# Adafruit_Feather_RP2040_Scorpio.net
KiCad netlist of a schematic drawn in EAGLE
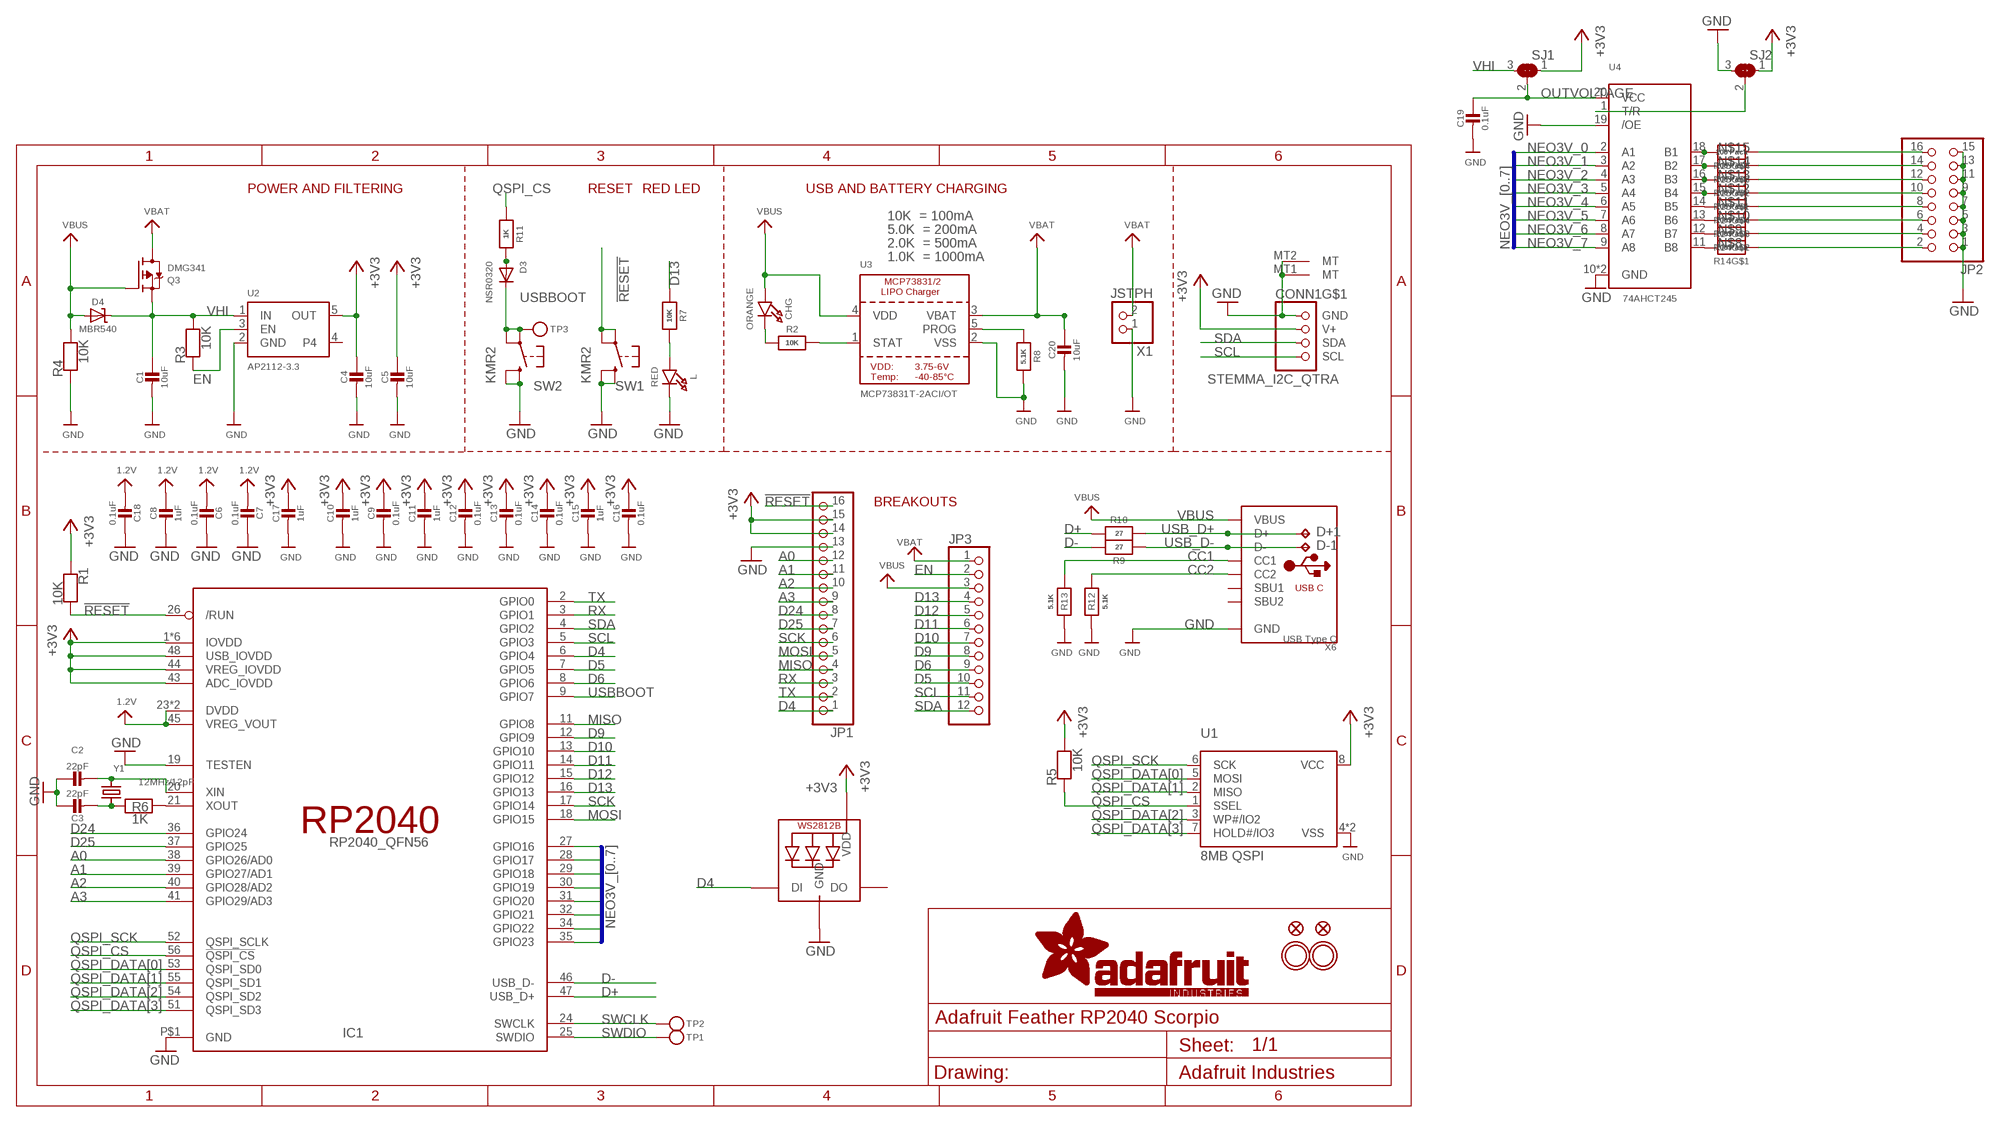
[diagram p0: schematic, sheet 1]

(export (version "E")
  (design (tool "Eeschema 10.0.6"))
  (components
    (comp (ref "C1")
      (value "10uF")
      (footprint "eagle-import:0805-NO")
      (libsource (lib "eagle-import") (part "CAP_CERAMIC0805-NOOUTLINE"))
    )
    (comp (ref "C2")
      (value "22pF")
      (footprint "eagle-import:_0402NO")
      (libsource (lib "eagle-import") (part "CAP_CERAMIC_0402NO"))
    )
    (comp (ref "C3")
      (value "22pF")
      (footprint "eagle-import:_0402NO")
      (libsource (lib "eagle-import") (part "CAP_CERAMIC_0402NO"))
    )
    (comp (ref "C4")
      (value "10uF")
      (footprint "eagle-import:0805-NO")
      (fields (field (name "REV") "A"))
      (libsource (lib "eagle-import") (part "CAP_CERAMIC0805-NOOUTLINE"))
    )
    (comp (ref "C5")
      (value "10uF")
      (footprint "eagle-import:0805-NO")
      (libsource (lib "eagle-import") (part "CAP_CERAMIC0805-NOOUTLINE"))
    )
    (comp (ref "C6")
      (value "0.1uF")
      (footprint "eagle-import:_0402NO")
      (libsource (lib "eagle-import") (part "CAP_CERAMIC_0402NO"))
    )
    (comp (ref "C7")
      (value "0.1uF")
      (footprint "eagle-import:_0402NO")
      (libsource (lib "eagle-import") (part "CAP_CERAMIC_0402NO"))
    )
    (comp (ref "C8")
      (value "1uF")
      (footprint "eagle-import:0603-NO")
      (libsource (lib "eagle-import") (part "CAP_CERAMIC0603_NO"))
    )
    (comp (ref "C9")
      (value "0.1uF")
      (footprint "eagle-import:_0402NO")
      (libsource (lib "eagle-import") (part "CAP_CERAMIC_0402NO"))
    )
    (comp (ref "C10")
      (value "1uF")
      (footprint "eagle-import:0603-NO")
      (libsource (lib "eagle-import") (part "CAP_CERAMIC0603_NO"))
    )
    (comp (ref "C11")
      (value "1uF")
      (footprint "eagle-import:0603-NO")
      (libsource (lib "eagle-import") (part "CAP_CERAMIC0603_NO"))
    )
    (comp (ref "C12")
      (value "0.1uF")
      (footprint "eagle-import:_0402NO")
      (libsource (lib "eagle-import") (part "CAP_CERAMIC_0402NO"))
    )
    (comp (ref "C13")
      (value "0.1uF")
      (footprint "eagle-import:_0402NO")
      (libsource (lib "eagle-import") (part "CAP_CERAMIC_0402NO"))
    )
    (comp (ref "C14")
      (value "0.1uF")
      (footprint "eagle-import:_0402NO")
      (libsource (lib "eagle-import") (part "CAP_CERAMIC_0402NO"))
    )
    (comp (ref "C15")
      (value "1uF")
      (footprint "eagle-import:0603-NO")
      (libsource (lib "eagle-import") (part "CAP_CERAMIC0603_NO"))
    )
    (comp (ref "C16")
      (value "0.1uF")
      (footprint "eagle-import:_0402NO")
      (libsource (lib "eagle-import") (part "CAP_CERAMIC_0402NO"))
    )
    (comp (ref "C17")
      (value "1uF")
      (footprint "eagle-import:0603-NO")
      (libsource (lib "eagle-import") (part "CAP_CERAMIC0603_NO"))
    )
    (comp (ref "C18")
      (value "0.1uF")
      (footprint "eagle-import:_0402NO")
      (libsource (lib "eagle-import") (part "CAP_CERAMIC_0402NO"))
    )
    (comp (ref "C19")
      (value "0.1uF")
      (footprint "eagle-import:_0402NO")
      (libsource (lib "eagle-import") (part "CAP_CERAMIC_0402NO"))
    )
    (comp (ref "C20")
      (value "10uF")
      (footprint "eagle-import:0805-NO")
      (libsource (lib "eagle-import") (part "CAP_CERAMIC0805-NOOUTLINE"))
    )
    (comp (ref "CHG")
      (value "ORANGE")
      (footprint "eagle-import:CHIPLED_0603_NOOUTLINE")
      (libsource (lib "eagle-import") (part "LED0603_NOOUTLINE"))
    )
    (comp (ref "CONN1")
      (value "STEMMA_I2C_QTRA")
      (footprint "eagle-import:JST_SH4_RA")
      (libsource (lib "eagle-import") (part "STEMMA_I2C_QTRA"))
    )
    (comp (ref "D+1")
      (value "TPB1,27")
      (footprint "eagle-import:B1,27")
      (libsource (lib "eagle-import") (part "TPB1,27"))
    )
    (comp (ref "D-1")
      (value "TPB1,27")
      (footprint "eagle-import:B1,27")
      (libsource (lib "eagle-import") (part "TPB1,27"))
    )
    (comp (ref "D3")
      (value "NSR0320")
      (footprint "eagle-import:SOD-323F")
      (libsource (lib "eagle-import") (part "DIODESOD-323F"))
    )
    (comp (ref "D4")
      (value "MBR540")
      (footprint "eagle-import:SOD-123")
      (libsource (lib "eagle-import") (part "DIODE-SCHOTTKYSOD-123"))
    )
    (comp (ref "IC1")
      (value "RP2040_QFN56")
      (footprint "eagle-import:QFN56_7MM_REDUCEDEPAD")
      (libsource (lib "eagle-import") (part "RP2040_QFN56"))
    )
    (comp (ref "JP1")
      (value "HEADER-1X16ROUND")
      (footprint "eagle-import:1X16_ROUND")
      (libsource (lib "eagle-import") (part "HEADER-1X16ROUND"))
    )
    (comp (ref "JP2")
      (value "HEADER-2X8")
      (footprint "eagle-import:2X08")
      (libsource (lib "eagle-import") (part "HEADER-2X8"))
    )
    (comp (ref "JP3")
      (value "HEADER-1X12")
      (footprint "eagle-import:1X12_ROUND")
      (libsource (lib "eagle-import") (part "HEADER-1X12"))
    )
    (comp (ref "L")
      (value "RED")
      (footprint "eagle-import:CHIPLED_0603_NOOUTLINE")
      (libsource (lib "eagle-import") (part "LED0603_NOOUTLINE"))
    )
    (comp (ref "LED1")
      (value "WS2812B_SK6805_1515")
      (footprint "eagle-import:SK6805_1515")
      (libsource (lib "eagle-import") (part "WS2812B_SK6805_1515"))
    )
    (comp (ref "Q3")
      (value "DMG341")
      (footprint "eagle-import:SOT23-R")
      (libsource (lib "eagle-import") (part "MOSFET-P"))
    )
    (comp (ref "R1")
      (value "10K")
      (footprint "eagle-import:0603-NO")
      (libsource (lib "eagle-import") (part "RESISTOR_0603_NOOUT"))
    )
    (comp (ref "R2")
      (value "10K")
      (footprint "eagle-import:0603-NO")
      (libsource (lib "eagle-import") (part "RESISTOR_0603_NOOUT"))
    )
    (comp (ref "R3")
      (value "10K")
      (footprint "eagle-import:0603-NO")
      (libsource (lib "eagle-import") (part "RESISTOR_0603_NOOUT"))
    )
    (comp (ref "R4")
      (value "10K")
      (footprint "eagle-import:0603-NO")
      (libsource (lib "eagle-import") (part "RESISTOR_0603_NOOUT"))
    )
    (comp (ref "R5")
      (value "10K")
      (footprint "eagle-import:0603-NO")
      (libsource (lib "eagle-import") (part "RESISTOR_0603_NOOUT"))
    )
    (comp (ref "R6")
      (value "1K")
      (footprint "eagle-import:0603-NO")
      (libsource (lib "eagle-import") (part "RESISTOR_0603_NOOUT"))
    )
    (comp (ref "R7")
      (value "10K")
      (footprint "eagle-import:0603-NO")
      (libsource (lib "eagle-import") (part "RESISTOR_0603_NOOUT"))
    )
    (comp (ref "R8")
      (value "5.1K")
      (footprint "eagle-import:0603-NO")
      (libsource (lib "eagle-import") (part "RESISTOR_0603_NOOUT"))
    )
    (comp (ref "R9")
      (value "27")
      (footprint "eagle-import:0603-NO")
      (libsource (lib "eagle-import") (part "RESISTOR_0603_NOOUT"))
    )
    (comp (ref "R10")
      (value "27")
      (footprint "eagle-import:0603-NO")
      (libsource (lib "eagle-import") (part "RESISTOR_0603_NOOUT"))
    )
    (comp (ref "R11")
      (value "1K")
      (footprint "eagle-import:0603-NO")
      (libsource (lib "eagle-import") (part "RESISTOR_0603_NOOUT"))
    )
    (comp (ref "R12")
      (value "5.1K")
      (footprint "eagle-import:0603-NO")
      (libsource (lib "eagle-import") (part "RESISTOR_0603_NOOUT"))
    )
    (comp (ref "R13")
      (value "5.1K")
      (footprint "eagle-import:0603-NO")
      (libsource (lib "eagle-import") (part "RESISTOR_0603_NOOUT"))
    )
    (comp (ref "R14")
      (value "100 Pack")
      (footprint "eagle-import:RESPACK_4X0402")
      (libsource (lib "eagle-import") (part "RESISTOR_4PACK_0804"))
    )
    (comp (ref "R15")
      (value "100 Pack")
      (footprint "eagle-import:RESPACK_4X0402")
      (libsource (lib "eagle-import") (part "RESISTOR_4PACK_0804"))
    )
    (comp (ref "SJ1")
      (value "SOLDERJUMPER_2WAY")
      (footprint "eagle-import:SOLDERJUMPER_2WAY_OPEN_NOPASTE")
      (libsource (lib "eagle-import") (part "SOLDERJUMPER_2WAY"))
    )
    (comp (ref "SJ2")
      (value "SOLDERJUMPER_2WAY")
      (footprint "eagle-import:SOLDERJUMPER_2WAY_OPEN_NOPASTE")
      (libsource (lib "eagle-import") (part "SOLDERJUMPER_2WAY"))
    )
    (comp (ref "SW1")
      (value "KMR2")
      (footprint "eagle-import:BTN_KMR2_4.6X2.8")
      (libsource (lib "eagle-import") (part "SWITCH_TACT_SMT4.6X2.8"))
    )
    (comp (ref "SW2")
      (value "KMR2")
      (footprint "eagle-import:BTN_KMR2_4.6X2.8")
      (libsource (lib "eagle-import") (part "SWITCH_TACT_SMT4.6X2.8"))
    )
    (comp (ref "TP1")
      (value "TESTPOINTROUND1.5MMNO")
      (footprint "eagle-import:TESTPOINT_ROUND_1.5MM_NO")
      (libsource (lib "eagle-import") (part "TESTPOINTROUND1.5MMNO"))
    )
    (comp (ref "TP2")
      (value "TESTPOINTROUND1.5MMNO")
      (footprint "eagle-import:TESTPOINT_ROUND_1.5MM_NO")
      (libsource (lib "eagle-import") (part "TESTPOINTROUND1.5MMNO"))
    )
    (comp (ref "TP3")
      (value "TESTPOINTROUND1.5MMNO")
      (footprint "eagle-import:TESTPOINT_ROUND_1.5MM_NO")
      (libsource (lib "eagle-import") (part "TESTPOINTROUND1.5MMNO"))
    )
    (comp (ref "U$31")
      (value "MOUNTINGHOLE2.5")
      (footprint "eagle-import:MOUNTINGHOLE_2.5_PLATED")
      (libsource (lib "eagle-import") (part "MOUNTINGHOLE2.5"))
    )
    (comp (ref "U$32")
      (value "MOUNTINGHOLE2.5")
      (footprint "eagle-import:MOUNTINGHOLE_2.5_PLATED")
      (libsource (lib "eagle-import") (part "MOUNTINGHOLE2.5"))
    )
    (comp (ref "U$34")
      (value "FIDUCIAL_1MM")
      (footprint "eagle-import:FIDUCIAL_1MM")
      (libsource (lib "eagle-import") (part "FIDUCIAL_1MM"))
    )
    (comp (ref "U$35")
      (value "FIDUCIAL_1MM")
      (footprint "eagle-import:FIDUCIAL_1MM")
      (libsource (lib "eagle-import") (part "FIDUCIAL_1MM"))
    )
    (comp (ref "U1")
      (value "8MB QSPI")
      (footprint "eagle-import:USON8_4X4")
      (libsource (lib "eagle-import") (part "SPIFLASH_8PIN_4X4"))
    )
    (comp (ref "U2")
      (value "AP2112-3.3")
      (footprint "eagle-import:SOT23-5")
      (fields (field (name "JLC_ROTATION") "0"))
      (libsource (lib "eagle-import") (part "VREG_SOT23-5"))
    )
    (comp (ref "U3")
      (value "MCP73831T-2ACI/OT")
      (footprint "eagle-import:SOT23-5")
      (libsource (lib "eagle-import") (part "MCP73831/2"))
    )
    (comp (ref "U4")
      (value "74AHCT245")
      (footprint "eagle-import:20-DHVQFN")
      (libsource (lib "eagle-import") (part "74LCX245_QFN20"))
    )
    (comp (ref "X1")
      (value "JSTPH")
      (footprint "eagle-import:JSTPH2_BATT")
      (libsource (lib "eagle-import") (part "CON_JST_PH_2PIN_BATT"))
    )
    (comp (ref "X6")
      (value "USB Type C")
      (footprint "eagle-import:USB_C_CUSB31-CFM2AX-01-X")
      (libsource (lib "eagle-import") (part "USB_C"))
    )
    (comp (ref "Y1")
      (value "12MHz/12pF")
      (footprint "eagle-import:CRYSTAL_2.5X2")
      (libsource (lib "eagle-import") (part "CRYSTAL2.5X2.0"))
    )
  )
  (nets
    (net (code "1") (name "+3V3") (class "Default")
      (node (ref "C10") (pin "1") (pinfunction "1_1") (pintype "passive"))
      (node (ref "C11") (pin "1") (pinfunction "1_1") (pintype "passive"))
      (node (ref "C12") (pin "1") (pinfunction "1_1") (pintype "passive"))
      (node (ref "C13") (pin "1") (pinfunction "1_1") (pintype "passive"))
      (node (ref "C14") (pin "1") (pinfunction "1_1") (pintype "passive"))
      (node (ref "C15") (pin "1") (pinfunction "1_1") (pintype "passive"))
      (node (ref "C16") (pin "1") (pinfunction "1_1") (pintype "passive"))
      (node (ref "C17") (pin "1") (pinfunction "1_1") (pintype "passive"))
      (node (ref "C4") (pin "1") (pinfunction "1_1") (pintype "passive"))
      (node (ref "C5") (pin "1") (pinfunction "1_1") (pintype "passive"))
      (node (ref "C9") (pin "1") (pinfunction "1_1") (pintype "passive"))
      (node (ref "CONN1") (pin "2") (pinfunction "V+_2") (pintype "passive"))
      (node (ref "IC1") (pin "1") (pinfunction "IOVDD_1") (pintype "power_in"))
      (node (ref "IC1") (pin "10") (pinfunction "IOVDD_10") (pintype "power_in"))
      (node (ref "IC1") (pin "22") (pinfunction "IOVDD_22") (pintype "power_in"))
      (node (ref "IC1") (pin "33") (pinfunction "IOVDD_33") (pintype "power_in"))
      (node (ref "IC1") (pin "42") (pinfunction "IOVDD_42") (pintype "power_in"))
      (node (ref "IC1") (pin "43") (pinfunction "ADC_IOVDD_43") (pintype "power_in"))
      (node (ref "IC1") (pin "44") (pinfunction "VREG_IOVDD_44") (pintype "power_in"))
      (node (ref "IC1") (pin "48") (pinfunction "USB_IOVDD_48") (pintype "power_in"))
      (node (ref "IC1") (pin "49") (pinfunction "IOVDD_49") (pintype "power_in"))
      (node (ref "JP1") (pin "14") (pinfunction "14_14") (pintype "passive"))
      (node (ref "JP1") (pin "15") (pinfunction "15_15") (pintype "passive"))
      (node (ref "LED1") (pin "2") (pinfunction "VDD_2") (pintype "power_in"))
      (node (ref "R1") (pin "1") (pinfunction "1_1") (pintype "passive"))
      (node (ref "R5") (pin "2") (pinfunction "2_2") (pintype "passive"))
      (node (ref "SJ1") (pin "1") (pinfunction "1_1") (pintype "passive"))
      (node (ref "SJ2") (pin "1") (pinfunction "1_1") (pintype "passive"))
      (node (ref "U1") (pin "8") (pinfunction "VCC_8") (pintype "bidirectional"))
      (node (ref "U2") (pin "5") (pinfunction "OUT_5") (pintype "power_in"))
    )
    (net (code "2") (name "/A0") (class "Default")
      (node (ref "IC1") (pin "38") (pinfunction "GPIO26/AD0_38") (pintype "bidirectional"))
      (node (ref "JP1") (pin "12") (pinfunction "12_12") (pintype "passive"))
    )
    (net (code "3") (name "/A1") (class "Default")
      (node (ref "IC1") (pin "39") (pinfunction "GPIO27/AD1_39") (pintype "bidirectional"))
      (node (ref "JP1") (pin "11") (pinfunction "11_11") (pintype "passive"))
    )
    (net (code "4") (name "/A2") (class "Default")
      (node (ref "IC1") (pin "40") (pinfunction "GPIO28/AD2_40") (pintype "bidirectional"))
      (node (ref "JP1") (pin "10") (pinfunction "10_10") (pintype "passive"))
    )
    (net (code "5") (name "/A3") (class "Default")
      (node (ref "IC1") (pin "41") (pinfunction "GPIO29/AD3_41") (pintype "bidirectional"))
      (node (ref "JP1") (pin "9") (pinfunction "9_9") (pintype "passive"))
    )
    (net (code "6") (name "/CC1") (class "Default")
      (node (ref "R13") (pin "2") (pinfunction "2_2") (pintype "passive"))
      (node (ref "X6") (pin "A5") (pinfunction "CC1_A5") (pintype "bidirectional"))
    )
    (net (code "7") (name "/CC2") (class "Default")
      (node (ref "R12") (pin "2") (pinfunction "2_2") (pintype "passive"))
      (node (ref "X6") (pin "B5") (pinfunction "CC2_B5") (pintype "bidirectional"))
    )
    (net (code "8") (name "/D+") (class "Default")
      (node (ref "IC1") (pin "47") (pinfunction "USB_D+_47") (pintype "bidirectional"))
      (node (ref "R10") (pin "2") (pinfunction "2_2") (pintype "passive"))
    )
    (net (code "9") (name "/D-") (class "Default")
      (node (ref "IC1") (pin "46") (pinfunction "USB_D-_46") (pintype "bidirectional"))
      (node (ref "R9") (pin "2") (pinfunction "2_2") (pintype "passive"))
    )
    (net (code "10") (name "/D4") (class "Default")
      (node (ref "IC1") (pin "6") (pinfunction "GPIO4_6") (pintype "bidirectional"))
      (node (ref "JP1") (pin "1") (pinfunction "1_1") (pintype "passive"))
      (node (ref "LED1") (pin "1") (pinfunction "DI_1") (pintype "input"))
    )
    (net (code "11") (name "/D5") (class "Default")
      (node (ref "IC1") (pin "7") (pinfunction "GPIO5_7") (pintype "bidirectional"))
      (node (ref "JP3") (pin "10") (pinfunction "10_10") (pintype "passive"))
    )
    (net (code "12") (name "/D6") (class "Default")
      (node (ref "IC1") (pin "8") (pinfunction "GPIO6_8") (pintype "bidirectional"))
      (node (ref "JP3") (pin "9") (pinfunction "9_9") (pintype "passive"))
    )
    (net (code "13") (name "/D9") (class "Default")
      (node (ref "IC1") (pin "12") (pinfunction "GPIO9_12") (pintype "bidirectional"))
      (node (ref "JP3") (pin "8") (pinfunction "8_8") (pintype "passive"))
    )
    (net (code "14") (name "/D10") (class "Default")
      (node (ref "IC1") (pin "13") (pinfunction "GPIO10_13") (pintype "bidirectional"))
      (node (ref "JP3") (pin "7") (pinfunction "7_7") (pintype "passive"))
    )
    (net (code "15") (name "/D11") (class "Default")
      (node (ref "IC1") (pin "14") (pinfunction "GPIO11_14") (pintype "bidirectional"))
      (node (ref "JP3") (pin "6") (pinfunction "6_6") (pintype "passive"))
    )
    (net (code "16") (name "/D12") (class "Default")
      (node (ref "IC1") (pin "15") (pinfunction "GPIO12_15") (pintype "bidirectional"))
      (node (ref "JP3") (pin "5") (pinfunction "5_5") (pintype "passive"))
    )
    (net (code "17") (name "/D13") (class "Default")
      (node (ref "IC1") (pin "16") (pinfunction "GPIO13_16") (pintype "bidirectional"))
      (node (ref "JP3") (pin "4") (pinfunction "4_4") (pintype "passive"))
      (node (ref "R7") (pin "1") (pinfunction "1_1") (pintype "passive"))
    )
    (net (code "18") (name "/D24") (class "Default")
      (node (ref "IC1") (pin "36") (pinfunction "GPIO24_36") (pintype "bidirectional"))
      (node (ref "JP1") (pin "8") (pinfunction "8_8") (pintype "passive"))
    )
    (net (code "19") (name "/D25") (class "Default")
      (node (ref "IC1") (pin "37") (pinfunction "GPIO25_37") (pintype "bidirectional"))
      (node (ref "JP1") (pin "7") (pinfunction "7_7") (pintype "passive"))
    )
    (net (code "20") (name "/EN") (class "Default")
      (node (ref "JP3") (pin "2") (pinfunction "2_2") (pintype "passive"))
      (node (ref "R3") (pin "1") (pinfunction "1_1") (pintype "passive"))
      (node (ref "U2") (pin "3") (pinfunction "EN_3") (pintype "input"))
    )
    (net (code "21") (name "/MISO") (class "Default")
      (node (ref "IC1") (pin "11") (pinfunction "GPIO8_11") (pintype "bidirectional"))
      (node (ref "JP1") (pin "4") (pinfunction "4_4") (pintype "passive"))
    )
    (net (code "22") (name "/MOSI") (class "Default")
      (node (ref "IC1") (pin "18") (pinfunction "GPIO15_18") (pintype "bidirectional"))
      (node (ref "JP1") (pin "5") (pinfunction "5_5") (pintype "passive"))
    )
    (net (code "31") (name "/NEO3V_0") (class "Default")
      (node (ref "IC1") (pin "27") (pinfunction "GPIO16_27") (pintype "bidirectional"))
      (node (ref "U4") (pin "2") (pinfunction "A1_2") (pintype "bidirectional"))
    )
    (net (code "32") (name "/NEO3V_1") (class "Default")
      (node (ref "IC1") (pin "28") (pinfunction "GPIO17_28") (pintype "bidirectional"))
      (node (ref "U4") (pin "3") (pinfunction "A2_3") (pintype "bidirectional"))
    )
    (net (code "33") (name "/NEO3V_2") (class "Default")
      (node (ref "IC1") (pin "29") (pinfunction "GPIO18_29") (pintype "bidirectional"))
      (node (ref "U4") (pin "4") (pinfunction "A3_4") (pintype "bidirectional"))
    )
    (net (code "34") (name "/NEO3V_3") (class "Default")
      (node (ref "IC1") (pin "30") (pinfunction "GPIO19_30") (pintype "bidirectional"))
      (node (ref "U4") (pin "5") (pinfunction "A4_5") (pintype "bidirectional"))
    )
    (net (code "35") (name "/NEO3V_4") (class "Default")
      (node (ref "IC1") (pin "31") (pinfunction "GPIO20_31") (pintype "bidirectional"))
      (node (ref "U4") (pin "6") (pinfunction "A5_6") (pintype "bidirectional"))
    )
    (net (code "36") (name "/NEO3V_5") (class "Default")
      (node (ref "IC1") (pin "32") (pinfunction "GPIO21_32") (pintype "bidirectional"))
      (node (ref "U4") (pin "7") (pinfunction "A6_7") (pintype "bidirectional"))
    )
    (net (code "37") (name "/NEO3V_6") (class "Default")
      (node (ref "IC1") (pin "34") (pinfunction "GPIO22_34") (pintype "bidirectional"))
      (node (ref "U4") (pin "8") (pinfunction "A7_8") (pintype "bidirectional"))
    )
    (net (code "38") (name "/NEO3V_7") (class "Default")
      (node (ref "IC1") (pin "35") (pinfunction "GPIO23_35") (pintype "bidirectional"))
      (node (ref "U4") (pin "9") (pinfunction "A8_9") (pintype "bidirectional"))
    )
    (net (code "40") (name "/OUTVOLTAGE") (class "Default")
      (node (ref "C19") (pin "1") (pinfunction "1_1") (pintype "passive"))
      (node (ref "SJ1") (pin "2") (pinfunction "2_2") (pintype "passive"))
      (node (ref "U4") (pin "20") (pinfunction "VCC_20") (pintype "bidirectional"))
    )
    (net (code "41") (name "/QSPI_CS") (class "Default")
      (node (ref "IC1") (pin "56") (pinfunction "~{QSPI_CS}_56") (pintype "bidirectional"))
      (node (ref "R11") (pin "1") (pinfunction "1_1") (pintype "passive"))
      (node (ref "R5") (pin "1") (pinfunction "1_1") (pintype "passive"))
      (node (ref "U1") (pin "1") (pinfunction "SSEL_1") (pintype "bidirectional"))
    )
    (net (code "42") (name "/QSPI_DATA[0]") (class "Default")
      (node (ref "IC1") (pin "53") (pinfunction "QSPI_SD0_53") (pintype "bidirectional"))
      (node (ref "U1") (pin "5") (pinfunction "MOSI_5") (pintype "bidirectional"))
    )
    (net (code "43") (name "/QSPI_DATA[1]") (class "Default")
      (node (ref "IC1") (pin "55") (pinfunction "QSPI_SD1_55") (pintype "bidirectional"))
      (node (ref "U1") (pin "2") (pinfunction "MISO_2") (pintype "bidirectional"))
    )
    (net (code "44") (name "/QSPI_DATA[2]") (class "Default")
      (node (ref "IC1") (pin "54") (pinfunction "QSPI_SD2_54") (pintype "bidirectional"))
      (node (ref "U1") (pin "3") (pinfunction "WP#/IO2_3") (pintype "bidirectional"))
    )
    (net (code "45") (name "/QSPI_DATA[3]") (class "Default")
      (node (ref "IC1") (pin "51") (pinfunction "QSPI_SD3_51") (pintype "bidirectional"))
      (node (ref "U1") (pin "7") (pinfunction "HOLD#/IO3_7") (pintype "bidirectional"))
    )
    (net (code "46") (name "/QSPI_SCK") (class "Default")
      (node (ref "IC1") (pin "52") (pinfunction "QSPI_SCLK_52") (pintype "bidirectional"))
      (node (ref "U1") (pin "6") (pinfunction "SCK_6") (pintype "bidirectional"))
    )
    (net (code "47") (name "/RX") (class "Default")
      (node (ref "IC1") (pin "3") (pinfunction "GPIO1_3") (pintype "bidirectional"))
      (node (ref "JP1") (pin "3") (pinfunction "3_3") (pintype "passive"))
    )
    (net (code "48") (name "/SCK") (class "Default")
      (node (ref "IC1") (pin "17") (pinfunction "GPIO14_17") (pintype "bidirectional"))
      (node (ref "JP1") (pin "6") (pinfunction "6_6") (pintype "passive"))
    )
    (net (code "49") (name "/SCL") (class "Default")
      (node (ref "CONN1") (pin "4") (pinfunction "SCL_4") (pintype "passive"))
      (node (ref "IC1") (pin "5") (pinfunction "GPIO3_5") (pintype "bidirectional"))
      (node (ref "JP3") (pin "11") (pinfunction "11_11") (pintype "passive"))
    )
    (net (code "50") (name "/SDA") (class "Default")
      (node (ref "CONN1") (pin "3") (pinfunction "SDA_3") (pintype "passive"))
      (node (ref "IC1") (pin "4") (pinfunction "GPIO2_4") (pintype "bidirectional"))
      (node (ref "JP3") (pin "12") (pinfunction "12_12") (pintype "passive"))
    )
    (net (code "51") (name "/SWCLK") (class "Default")
      (node (ref "IC1") (pin "24") (pinfunction "SWCLK_24") (pintype "bidirectional"))
      (node (ref "TP2") (pin "P$1") (pinfunction "P$1_P$1") (pintype "bidirectional"))
    )
    (net (code "52") (name "/SWDIO") (class "Default")
      (node (ref "IC1") (pin "25") (pinfunction "SWDIO_25") (pintype "bidirectional"))
      (node (ref "TP1") (pin "P$1") (pinfunction "P$1_P$1") (pintype "bidirectional"))
    )
    (net (code "53") (name "/TX") (class "Default")
      (node (ref "IC1") (pin "2") (pinfunction "GPIO0_2") (pintype "bidirectional"))
      (node (ref "JP1") (pin "2") (pinfunction "2_2") (pintype "passive"))
    )
    (net (code "54") (name "/USBBOOT") (class "Default")
      (node (ref "D3") (pin "C") (pinfunction "C_C") (pintype "passive"))
      (node (ref "IC1") (pin "9") (pinfunction "GPIO7_9") (pintype "bidirectional"))
      (node (ref "SW2") (pin "A") (pinfunction "P_A") (pintype "passive"))
      (node (ref "SW2") (pin "A'") (pinfunction "P1_A'") (pintype "passive"))
      (node (ref "TP3") (pin "P$1") (pinfunction "P$1_P$1") (pintype "bidirectional"))
    )
    (net (code "55") (name "/USB_D+") (class "Default")
      (node (ref "D+1") (pin "TP") (pinfunction "TP_TP") (pintype "input"))
      (node (ref "R10") (pin "1") (pinfunction "1_1") (pintype "passive"))
      (node (ref "X6") (pin "A6") (pinfunction "D+_A6") (pintype "bidirectional"))
      (node (ref "X6") (pin "B6") (pinfunction "D+_B6") (pintype "bidirectional"))
    )
    (net (code "56") (name "/USB_D-") (class "Default")
      (node (ref "D-1") (pin "TP") (pinfunction "TP_TP") (pintype "input"))
      (node (ref "R9") (pin "1") (pinfunction "1_1") (pintype "passive"))
      (node (ref "X6") (pin "A7") (pinfunction "D-_A7") (pintype "bidirectional"))
      (node (ref "X6") (pin "B7") (pinfunction "D-_B7") (pintype "bidirectional"))
    )
    (net (code "57") (name "/VHI") (class "Default")
      (node (ref "C1") (pin "1") (pinfunction "1_1") (pintype "passive"))
      (node (ref "D4") (pin "C") (pinfunction "C_C") (pintype "passive"))
      (node (ref "Q3") (pin "2") (pinfunction "S_2") (pintype "passive"))
      (node (ref "R3") (pin "2") (pinfunction "2_2") (pintype "passive"))
      (node (ref "SJ1") (pin "3") (pinfunction "3_3") (pintype "passive"))
      (node (ref "U2") (pin "1") (pinfunction "IN_1") (pintype "power_in"))
    )
    (net (code "58") (name "/~{RESET}") (class "Default")
      (node (ref "IC1") (pin "26") (pinfunction "/RUN_26") (pintype "bidirectional"))
      (node (ref "JP1") (pin "16") (pinfunction "16_16") (pintype "passive"))
      (node (ref "R1") (pin "2") (pinfunction "2_2") (pintype "passive"))
      (node (ref "SW1") (pin "A") (pinfunction "P_A") (pintype "passive"))
      (node (ref "SW1") (pin "A'") (pinfunction "P1_A'") (pintype "passive"))
    )
    (net (code "59") (name "1.2V") (class "Default")
      (node (ref "C18") (pin "2") (pinfunction "2_2") (pintype "passive"))
      (node (ref "C6") (pin "2") (pinfunction "2_2") (pintype "passive"))
      (node (ref "C7") (pin "2") (pinfunction "2_2") (pintype "passive"))
      (node (ref "C8") (pin "1") (pinfunction "1_1") (pintype "passive"))
      (node (ref "IC1") (pin "23") (pinfunction "DVDD_23") (pintype "power_in"))
      (node (ref "IC1") (pin "45") (pinfunction "VREG_VOUT_45") (pintype "power_in"))
      (node (ref "IC1") (pin "50") (pinfunction "DVDD_50") (pintype "power_in"))
    )
    (net (code "60") (name "GND") (class "Default")
      (node (ref "C1") (pin "2") (pinfunction "2_2") (pintype "passive"))
      (node (ref "C10") (pin "2") (pinfunction "2_2") (pintype "passive"))
      (node (ref "C11") (pin "2") (pinfunction "2_2") (pintype "passive"))
      (node (ref "C12") (pin "2") (pinfunction "2_2") (pintype "passive"))
      (node (ref "C13") (pin "2") (pinfunction "2_2") (pintype "passive"))
      (node (ref "C14") (pin "2") (pinfunction "2_2") (pintype "passive"))
      (node (ref "C15") (pin "2") (pinfunction "2_2") (pintype "passive"))
      (node (ref "C16") (pin "2") (pinfunction "2_2") (pintype "passive"))
      (node (ref "C17") (pin "2") (pinfunction "2_2") (pintype "passive"))
      (node (ref "C18") (pin "1") (pinfunction "1_1") (pintype "passive"))
      (node (ref "C19") (pin "2") (pinfunction "2_2") (pintype "passive"))
      (node (ref "C2") (pin "1") (pinfunction "1_1") (pintype "passive"))
      (node (ref "C20") (pin "2") (pinfunction "2_2") (pintype "passive"))
      (node (ref "C3") (pin "1") (pinfunction "1_1") (pintype "passive"))
      (node (ref "C4") (pin "2") (pinfunction "2_2") (pintype "passive"))
      (node (ref "C5") (pin "2") (pinfunction "2_2") (pintype "passive"))
      (node (ref "C6") (pin "1") (pinfunction "1_1") (pintype "passive"))
      (node (ref "C7") (pin "1") (pinfunction "1_1") (pintype "passive"))
      (node (ref "C8") (pin "2") (pinfunction "2_2") (pintype "passive"))
      (node (ref "C9") (pin "2") (pinfunction "2_2") (pintype "passive"))
      (node (ref "CONN1") (pin "1") (pinfunction "GND_1") (pintype "passive"))
      (node (ref "CONN1") (pin "MT1") (pinfunction "MT_MT1") (pintype "bidirectional"))
      (node (ref "CONN1") (pin "MT2") (pinfunction "MT_MT2") (pintype "bidirectional"))
      (node (ref "IC1") (pin "19") (pinfunction "TESTEN_19") (pintype "input"))
      (node (ref "IC1") (pin "P$1") (pinfunction "GND_P$1") (pintype "power_in"))
      (node (ref "JP1") (pin "13") (pinfunction "13_13") (pintype "passive"))
      (node (ref "JP2") (pin "1") (pinfunction "1_1") (pintype "passive"))
      (node (ref "JP2") (pin "11") (pinfunction "11_11") (pintype "passive"))
      (node (ref "JP2") (pin "13") (pinfunction "13_13") (pintype "passive"))
      (node (ref "JP2") (pin "15") (pinfunction "15_15") (pintype "passive"))
      (node (ref "JP2") (pin "3") (pinfunction "3_3") (pintype "passive"))
      (node (ref "JP2") (pin "5") (pinfunction "5_5") (pintype "passive"))
      (node (ref "JP2") (pin "7") (pinfunction "7_7") (pintype "passive"))
      (node (ref "JP2") (pin "9") (pinfunction "9_9") (pintype "passive"))
      (node (ref "L") (pin "C") (pinfunction "C_C") (pintype "passive"))
      (node (ref "LED1") (pin "4") (pinfunction "GND_4") (pintype "power_in"))
      (node (ref "R12") (pin "1") (pinfunction "1_1") (pintype "passive"))
      (node (ref "R13") (pin "1") (pinfunction "1_1") (pintype "passive"))
      (node (ref "R4") (pin "1") (pinfunction "1_1") (pintype "passive"))
      (node (ref "R8") (pin "2") (pinfunction "2_2") (pintype "passive"))
      (node (ref "SJ2") (pin "3") (pinfunction "3_3") (pintype "passive"))
      (node (ref "SW1") (pin "B") (pinfunction "S_B") (pintype "passive"))
      (node (ref "SW1") (pin "B'") (pinfunction "S1_B'") (pintype "passive"))
      (node (ref "SW2") (pin "B") (pinfunction "S_B") (pintype "passive"))
      (node (ref "SW2") (pin "B'") (pinfunction "S1_B'") (pintype "passive"))
      (node (ref "U1") (pin "4") (pinfunction "VSS_4") (pintype "bidirectional"))
      (node (ref "U1") (pin "PAD") (pinfunction "VSS_PAD") (pintype "bidirectional"))
      (node (ref "U2") (pin "2") (pinfunction "GND_2") (pintype "power_in"))
      (node (ref "U3") (pin "2") (pinfunction "VSS_2") (pintype "power_in"))
      (node (ref "U4") (pin "10") (pinfunction "GND_10") (pintype "bidirectional"))
      (node (ref "U4") (pin "19") (pinfunction "/OE_19") (pintype "bidirectional"))
      (node (ref "U4") (pin "21") (pinfunction "GND_21") (pintype "bidirectional"))
      (node (ref "X1") (pin "1") (pinfunction "1_1") (pintype "passive"))
      (node (ref "X6") (pin "A1B12") (pinfunction "GND_A1B12") (pintype "power_in"))
      (node (ref "X6") (pin "B1A12") (pinfunction "GND_B1A12") (pintype "power_in"))
    )
    (net (code "61") (name "Net-(C3-Pad2)") (class "Default")
      (node (ref "C3") (pin "2") (pinfunction "2_2") (pintype "passive"))
      (node (ref "R6") (pin "1") (pinfunction "1_1") (pintype "passive"))
      (node (ref "Y1") (pin "1") (pinfunction "1_1") (pintype "passive"))
    )
    (net (code "62") (name "Net-(CHG-PadC)") (class "Default")
      (node (ref "CHG") (pin "C") (pinfunction "C_C") (pintype "passive"))
      (node (ref "R2") (pin "1") (pinfunction "1_1") (pintype "passive"))
    )
    (net (code "63") (name "Net-(D3-PadA)") (class "Default")
      (node (ref "D3") (pin "A") (pinfunction "A_A") (pintype "passive"))
      (node (ref "R11") (pin "2") (pinfunction "2_2") (pintype "passive"))
    )
    (net (code "64") (name "Net-(IC1-XIN)") (class "Default")
      (node (ref "C2") (pin "2") (pinfunction "2_2") (pintype "passive"))
      (node (ref "IC1") (pin "20") (pinfunction "XIN_20") (pintype "input"))
      (node (ref "Y1") (pin "3") (pinfunction "2_3") (pintype "passive"))
    )
    (net (code "65") (name "Net-(IC1-XOUT)") (class "Default")
      (node (ref "IC1") (pin "21") (pinfunction "XOUT_21") (pintype "output"))
      (node (ref "R6") (pin "2") (pinfunction "2_2") (pintype "passive"))
    )
    (net (code "66") (name "Net-(JP2-Pad2)") (class "Default")
      (node (ref "JP2") (pin "2") (pinfunction "2_2") (pintype "passive"))
      (node (ref "R14") (pin "1") (pinfunction "1_1") (pintype "passive"))
    )
    (net (code "67") (name "Net-(JP2-Pad10)") (class "Default")
      (node (ref "JP2") (pin "10") (pinfunction "10_10") (pintype "passive"))
      (node (ref "R15") (pin "1") (pinfunction "1_1") (pintype "passive"))
    )
    (net (code "68") (name "Net-(L-PadA)") (class "Default")
      (node (ref "L") (pin "A") (pinfunction "A_A") (pintype "passive"))
      (node (ref "R7") (pin "2") (pinfunction "2_2") (pintype "passive"))
    )
    (net (code "69") (name "Net-(R14A-2)") (class "Default")
      (node (ref "R14") (pin "8") (pinfunction "2_8") (pintype "passive"))
      (node (ref "U4") (pin "11") (pinfunction "B8_11") (pintype "bidirectional"))
    )
    (net (code "70") (name "Net-(R14B-1)") (class "Default")
      (node (ref "JP2") (pin "4") (pinfunction "4_4") (pintype "passive"))
      (node (ref "R14") (pin "2") (pinfunction "1_2") (pintype "passive"))
    )
    (net (code "71") (name "Net-(R14B-2)") (class "Default")
      (node (ref "R14") (pin "7") (pinfunction "2_7") (pintype "passive"))
      (node (ref "U4") (pin "12") (pinfunction "B7_12") (pintype "bidirectional"))
    )
    (net (code "72") (name "Net-(R14C-1)") (class "Default")
      (node (ref "JP2") (pin "6") (pinfunction "6_6") (pintype "passive"))
      (node (ref "R14") (pin "3") (pinfunction "1_3") (pintype "passive"))
    )
    (net (code "73") (name "Net-(R14C-2)") (class "Default")
      (node (ref "R14") (pin "6") (pinfunction "2_6") (pintype "passive"))
      (node (ref "U4") (pin "13") (pinfunction "B6_13") (pintype "bidirectional"))
    )
    (net (code "74") (name "Net-(R14D-1)") (class "Default")
      (node (ref "JP2") (pin "8") (pinfunction "8_8") (pintype "passive"))
      (node (ref "R14") (pin "4") (pinfunction "1_4") (pintype "passive"))
    )
    (net (code "75") (name "Net-(R14D-2)") (class "Default")
      (node (ref "R14") (pin "5") (pinfunction "2_5") (pintype "passive"))
      (node (ref "U4") (pin "14") (pinfunction "B5_14") (pintype "bidirectional"))
    )
    (net (code "76") (name "Net-(R15A-2)") (class "Default")
      (node (ref "R15") (pin "8") (pinfunction "2_8") (pintype "passive"))
      (node (ref "U4") (pin "15") (pinfunction "B4_15") (pintype "bidirectional"))
    )
    (net (code "77") (name "Net-(R15B-1)") (class "Default")
      (node (ref "JP2") (pin "12") (pinfunction "12_12") (pintype "passive"))
      (node (ref "R15") (pin "2") (pinfunction "1_2") (pintype "passive"))
    )
    (net (code "78") (name "Net-(R15B-2)") (class "Default")
      (node (ref "R15") (pin "7") (pinfunction "2_7") (pintype "passive"))
      (node (ref "U4") (pin "16") (pinfunction "B3_16") (pintype "bidirectional"))
    )
    (net (code "79") (name "Net-(R15C-1)") (class "Default")
      (node (ref "JP2") (pin "14") (pinfunction "14_14") (pintype "passive"))
      (node (ref "R15") (pin "3") (pinfunction "1_3") (pintype "passive"))
    )
    (net (code "80") (name "Net-(R15C-2)") (class "Default")
      (node (ref "R15") (pin "6") (pinfunction "2_6") (pintype "passive"))
      (node (ref "U4") (pin "17") (pinfunction "B2_17") (pintype "bidirectional"))
    )
    (net (code "81") (name "Net-(R15D-1)") (class "Default")
      (node (ref "JP2") (pin "16") (pinfunction "16_16") (pintype "passive"))
      (node (ref "R15") (pin "4") (pinfunction "1_4") (pintype "passive"))
    )
    (net (code "82") (name "Net-(R15D-2)") (class "Default")
      (node (ref "R15") (pin "5") (pinfunction "2_5") (pintype "passive"))
      (node (ref "U4") (pin "18") (pinfunction "B1_18") (pintype "bidirectional"))
    )
    (net (code "83") (name "Net-(U3-PROG)") (class "Default")
      (node (ref "R8") (pin "1") (pinfunction "1_1") (pintype "passive"))
      (node (ref "U3") (pin "5") (pinfunction "PROG_5") (pintype "input"))
    )
    (net (code "84") (name "Net-(U3-STAT)") (class "Default")
      (node (ref "R2") (pin "2") (pinfunction "2_2") (pintype "passive"))
      (node (ref "U3") (pin "1") (pinfunction "STAT_1") (pintype "output"))
    )
    (net (code "85") (name "Net-(U4-T{slash}R)") (class "Default")
      (node (ref "SJ2") (pin "2") (pinfunction "2_2") (pintype "passive"))
      (node (ref "U4") (pin "1") (pinfunction "T/R_1") (pintype "bidirectional"))
    )
    (net (code "86") (name "VBAT") (class "Default")
      (node (ref "C20") (pin "1") (pinfunction "1_1") (pintype "passive"))
      (node (ref "JP3") (pin "1") (pinfunction "1_1") (pintype "passive"))
      (node (ref "Q3") (pin "3") (pinfunction "D_3") (pintype "passive"))
      (node (ref "U3") (pin "3") (pinfunction "VBAT_3") (pintype "power_in"))
      (node (ref "X1") (pin "2") (pinfunction "2_2") (pintype "passive"))
    )
    (net (code "87") (name "VBUS") (class "Default")
      (node (ref "CHG") (pin "A") (pinfunction "A_A") (pintype "passive"))
      (node (ref "D4") (pin "A") (pinfunction "A_A") (pintype "passive"))
      (node (ref "JP3") (pin "3") (pinfunction "3_3") (pintype "passive"))
      (node (ref "Q3") (pin "1") (pinfunction "G_1") (pintype "passive"))
      (node (ref "R4") (pin "2") (pinfunction "2_2") (pintype "passive"))
      (node (ref "U3") (pin "4") (pinfunction "VDD_4") (pintype "power_in"))
      (node (ref "X6") (pin "A4B9") (pinfunction "VBUS_A4B9") (pintype "power_in"))
      (node (ref "X6") (pin "B4A9") (pinfunction "VBUS_B4A9") (pintype "power_in"))
    )
    (net (code "88") (name "unconnected-(LED1-DO-Pad3)") (class "Default")
      (node (ref "LED1") (pin "3") (pinfunction "DO_3") (pintype "output"))
    )
    (net (code "89") (name "unconnected-(U2-P4-Pad4)") (class "Default")
      (node (ref "U2") (pin "4") (pinfunction "P4_4") (pintype "bidirectional"))
    )
    (net (code "90") (name "unconnected-(X6-SBU1-PadA8)") (class "Default")
      (node (ref "X6") (pin "A8") (pinfunction "SBU1_A8") (pintype "bidirectional"))
    )
    (net (code "91") (name "unconnected-(X6-SBU2-PadB8)") (class "Default")
      (node (ref "X6") (pin "B8") (pinfunction "SBU2_B8") (pintype "bidirectional"))
    )
  )
)
